# Dual_LPF_V1_2_Top.net
KiCad netlist of a schematic drawn in EAGLE
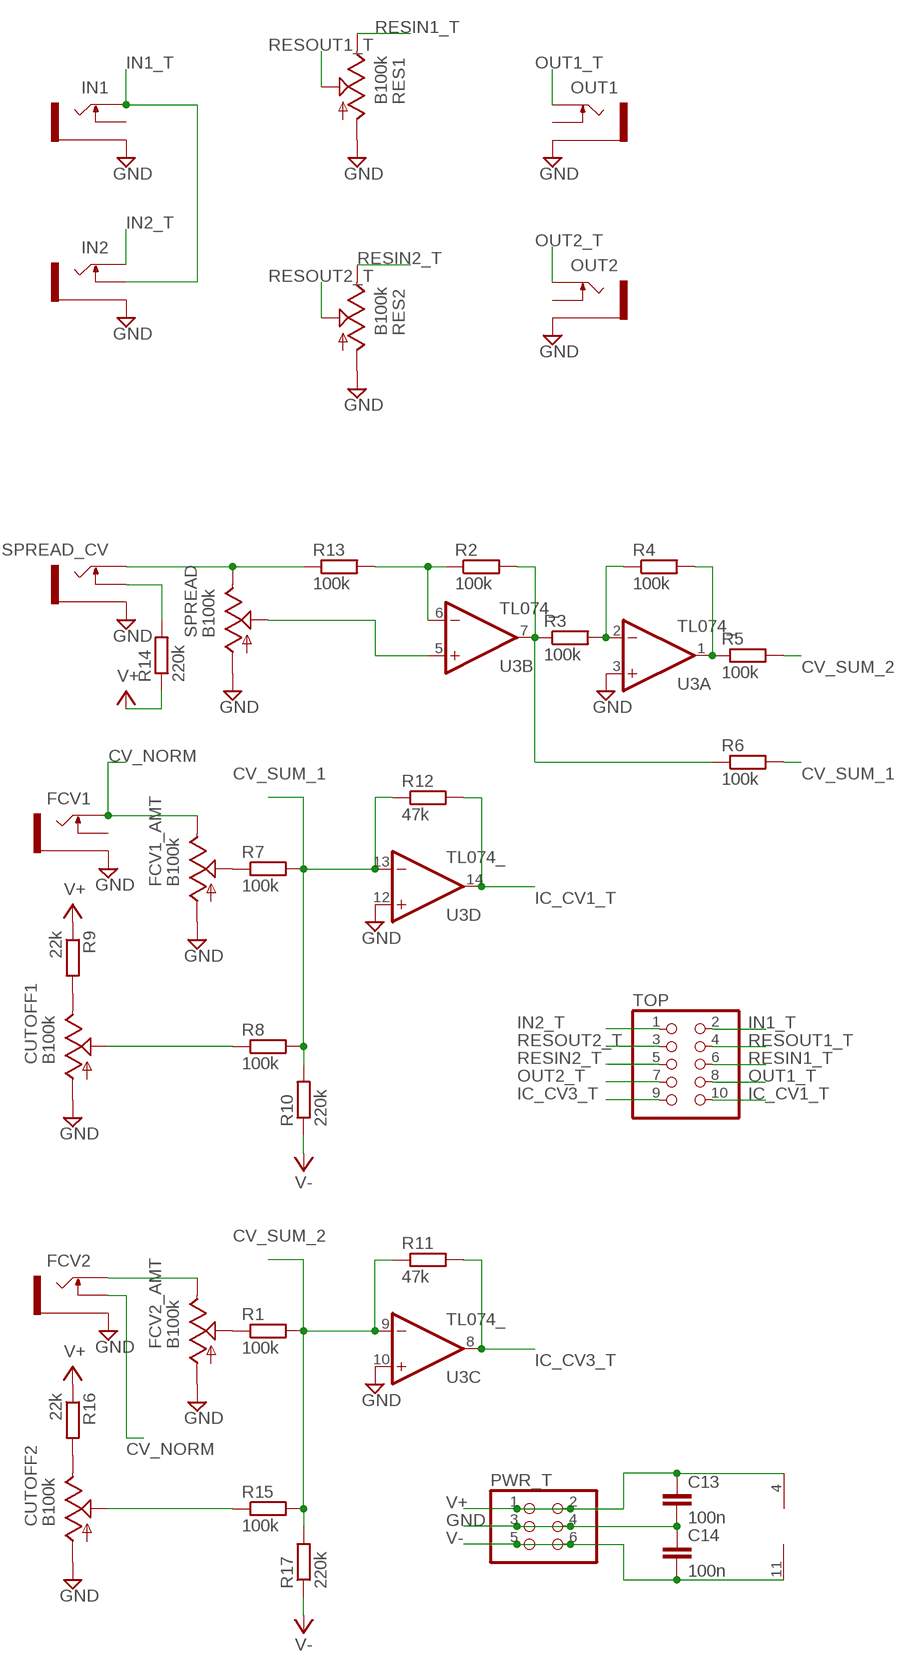
[diagram p0: schematic, sheet 1]

(export (version "E")
  (design (tool "Eeschema 10.0.6"))
  (components
    (comp (ref "C13")
      (value "100n")
      (footprint "eagle-import:C050-024X044")
      (libsource (lib "eagle-import") (part "C-EU050-024X044"))
    )
    (comp (ref "C14")
      (value "100n")
      (footprint "eagle-import:C050-024X044")
      (libsource (lib "eagle-import") (part "C-EU050-024X044"))
    )
    (comp (ref "CUTOFF1")
      (value "B100k")
      (footprint "eagle-import:9MM_SNAP-IN_POT")
      (libsource (lib "eagle-import") (part "9MM_SNAP-IN_POT_"))
    )
    (comp (ref "CUTOFF2")
      (value "B100k")
      (footprint "eagle-import:9MM_SNAP-IN_POT")
      (libsource (lib "eagle-import") (part "9MM_SNAP-IN_POT_"))
    )
    (comp (ref "FCV1")
      (value "THONKICONNNEW")
      (footprint "eagle-import:WQP-PJ301M-12_JACK")
      (libsource (lib "eagle-import") (part "THONKICONNNEW"))
    )
    (comp (ref "FCV1_AMT")
      (value "B100k")
      (footprint "eagle-import:9MM_SNAP-IN_POT")
      (libsource (lib "eagle-import") (part "9MM_SNAP-IN_POT_"))
    )
    (comp (ref "FCV2")
      (value "THONKICONNNEW")
      (footprint "eagle-import:WQP-PJ301M-12_JACK")
      (libsource (lib "eagle-import") (part "THONKICONNNEW"))
    )
    (comp (ref "FCV2_AMT")
      (value "B100k")
      (footprint "eagle-import:9MM_SNAP-IN_POT")
      (libsource (lib "eagle-import") (part "9MM_SNAP-IN_POT_"))
    )
    (comp (ref "IN1")
      (value "THONKICONNNEW")
      (footprint "eagle-import:WQP-PJ301M-12_JACK")
      (libsource (lib "eagle-import") (part "THONKICONNNEW"))
    )
    (comp (ref "IN2")
      (value "THONKICONNNEW")
      (footprint "eagle-import:WQP-PJ301M-12_JACK")
      (libsource (lib "eagle-import") (part "THONKICONNNEW"))
    )
    (comp (ref "OUT1")
      (value "THONKICONNNEW")
      (footprint "eagle-import:WQP-PJ301M-12_JACK")
      (libsource (lib "eagle-import") (part "THONKICONNNEW"))
    )
    (comp (ref "OUT2")
      (value "THONKICONNNEW")
      (footprint "eagle-import:WQP-PJ301M-12_JACK")
      (libsource (lib "eagle-import") (part "THONKICONNNEW"))
    )
    (comp (ref "PWR_T")
      (value "PINHD-2X3")
      (footprint "eagle-import:2X03")
      (libsource (lib "eagle-import") (part "PINHD-2X3"))
    )
    (comp (ref "R1")
      (value "100k")
      (footprint "eagle-import:0207_7")
      (libsource (lib "eagle-import") (part "R-EU_0207/7"))
    )
    (comp (ref "R2")
      (value "100k")
      (footprint "eagle-import:0207_7")
      (libsource (lib "eagle-import") (part "R-EU_0207/7"))
    )
    (comp (ref "R3")
      (value "100k")
      (footprint "eagle-import:0207_7")
      (libsource (lib "eagle-import") (part "R-EU_0207/7"))
    )
    (comp (ref "R4")
      (value "100k")
      (footprint "eagle-import:0207_7")
      (libsource (lib "eagle-import") (part "R-EU_0207/7"))
    )
    (comp (ref "R5")
      (value "100k")
      (footprint "eagle-import:0207_7")
      (libsource (lib "eagle-import") (part "R-EU_0207/7"))
    )
    (comp (ref "R6")
      (value "100k")
      (footprint "eagle-import:0207_7")
      (libsource (lib "eagle-import") (part "R-EU_0207/7"))
    )
    (comp (ref "R7")
      (value "100k")
      (footprint "eagle-import:0207_7")
      (libsource (lib "eagle-import") (part "R-EU_0207/7"))
    )
    (comp (ref "R8")
      (value "100k")
      (footprint "eagle-import:0207_7")
      (libsource (lib "eagle-import") (part "R-EU_0207/7"))
    )
    (comp (ref "R9")
      (value "22k")
      (footprint "eagle-import:0207_7")
      (libsource (lib "eagle-import") (part "R-EU_0207/7"))
    )
    (comp (ref "R10")
      (value "220k")
      (footprint "eagle-import:0207_7")
      (libsource (lib "eagle-import") (part "R-EU_0207/7"))
    )
    (comp (ref "R11")
      (value "47k")
      (footprint "eagle-import:0207_7")
      (libsource (lib "eagle-import") (part "R-EU_0207/7"))
    )
    (comp (ref "R12")
      (value "47k")
      (footprint "eagle-import:0207_7")
      (libsource (lib "eagle-import") (part "R-EU_0207/7"))
    )
    (comp (ref "R13")
      (value "100k")
      (footprint "eagle-import:0207_7")
      (libsource (lib "eagle-import") (part "R-EU_0207/7"))
    )
    (comp (ref "R14")
      (value "220k")
      (footprint "eagle-import:0207_7")
      (libsource (lib "eagle-import") (part "R-EU_0207/7"))
    )
    (comp (ref "R15")
      (value "100k")
      (footprint "eagle-import:0207_7")
      (libsource (lib "eagle-import") (part "R-EU_0207/7"))
    )
    (comp (ref "R16")
      (value "22k")
      (footprint "eagle-import:0207_7")
      (libsource (lib "eagle-import") (part "R-EU_0207/7"))
    )
    (comp (ref "R17")
      (value "220k")
      (footprint "eagle-import:0207_7")
      (libsource (lib "eagle-import") (part "R-EU_0207/7"))
    )
    (comp (ref "RES1")
      (value "B100k")
      (footprint "eagle-import:9MM_SNAP-IN_POT")
      (libsource (lib "eagle-import") (part "9MM_SNAP-IN_POT_"))
    )
    (comp (ref "RES2")
      (value "B100k")
      (footprint "eagle-import:9MM_SNAP-IN_POT")
      (libsource (lib "eagle-import") (part "9MM_SNAP-IN_POT_"))
    )
    (comp (ref "SPREAD")
      (value "B100k")
      (footprint "eagle-import:9MM_SNAP-IN_POT")
      (libsource (lib "eagle-import") (part "9MM_SNAP-IN_POT_"))
    )
    (comp (ref "SPREAD_CV")
      (value "THONKICONNNEW")
      (footprint "eagle-import:WQP-PJ301M-12_JACK")
      (libsource (lib "eagle-import") (part "THONKICONNNEW"))
    )
    (comp (ref "TOP")
      (value "PINHD-2X5")
      (footprint "eagle-import:2X05")
      (libsource (lib "eagle-import") (part "PINHD-2X5"))
    )
    (comp (ref "U3")
      (value "TL074_")
      (footprint "eagle-import:DIL14")
      (libsource (lib "eagle-import") (part "TL074_"))
    )
  )
  (nets
    (net (code "1") (name "/CV_NORM") (class "Default")
      (node (ref "FCV1") (pin "P$1_TIP") (pinfunction "TIP_P$1_TIP") (pintype "passive"))
      (node (ref "FCV1_AMT") (pin "3") (pinfunction "E_3") (pintype "passive"))
      (node (ref "FCV2") (pin "P$2_SWITCH") (pinfunction "SWITCH_P$2_SWITCH") (pintype "passive"))
    )
    (net (code "2") (name "/CV_SUM_1") (class "Default")
      (node (ref "R10") (pin "2") (pinfunction "2_2") (pintype "passive"))
      (node (ref "R12") (pin "1") (pinfunction "1_1") (pintype "passive"))
      (node (ref "R6") (pin "2") (pinfunction "2_2") (pintype "passive"))
      (node (ref "R7") (pin "2") (pinfunction "2_2") (pintype "passive"))
      (node (ref "R8") (pin "2") (pinfunction "2_2") (pintype "passive"))
      (node (ref "U3") (pin "13") (pinfunction "-IN_13") (pintype "input"))
    )
    (net (code "3") (name "/CV_SUM_2") (class "Default")
      (node (ref "R1") (pin "2") (pinfunction "2_2") (pintype "passive"))
      (node (ref "R11") (pin "1") (pinfunction "1_1") (pintype "passive"))
      (node (ref "R15") (pin "2") (pinfunction "2_2") (pintype "passive"))
      (node (ref "R17") (pin "2") (pinfunction "2_2") (pintype "passive"))
      (node (ref "R5") (pin "2") (pinfunction "2_2") (pintype "passive"))
      (node (ref "U3") (pin "9") (pinfunction "-IN_9") (pintype "input"))
    )
    (net (code "4") (name "/IC_CV1_T") (class "Default")
      (node (ref "R12") (pin "2") (pinfunction "2_2") (pintype "passive"))
      (node (ref "TOP") (pin "10") (pinfunction "10_10") (pintype "passive"))
      (node (ref "U3") (pin "14") (pinfunction "OUT_14") (pintype "output"))
    )
    (net (code "5") (name "/IC_CV3_T") (class "Default")
      (node (ref "R11") (pin "2") (pinfunction "2_2") (pintype "passive"))
      (node (ref "TOP") (pin "9") (pinfunction "9_9") (pintype "passive"))
      (node (ref "U3") (pin "8") (pinfunction "OUT_8") (pintype "output"))
    )
    (net (code "6") (name "/IN1_T") (class "Default")
      (node (ref "IN1") (pin "P$1_TIP") (pinfunction "TIP_P$1_TIP") (pintype "passive"))
      (node (ref "IN2") (pin "P$2_SWITCH") (pinfunction "SWITCH_P$2_SWITCH") (pintype "passive"))
      (node (ref "TOP") (pin "2") (pinfunction "2_2") (pintype "passive"))
    )
    (net (code "7") (name "/IN2_T") (class "Default")
      (node (ref "IN2") (pin "P$1_TIP") (pinfunction "TIP_P$1_TIP") (pintype "passive"))
      (node (ref "TOP") (pin "1") (pinfunction "1_1") (pintype "passive"))
    )
    (net (code "8") (name "/OUT1_T") (class "Default")
      (node (ref "OUT1") (pin "P$1_TIP") (pinfunction "TIP_P$1_TIP") (pintype "passive"))
      (node (ref "TOP") (pin "8") (pinfunction "8_8") (pintype "passive"))
    )
    (net (code "9") (name "/OUT2_T") (class "Default")
      (node (ref "OUT2") (pin "P$1_TIP") (pinfunction "TIP_P$1_TIP") (pintype "passive"))
      (node (ref "TOP") (pin "7") (pinfunction "7_7") (pintype "passive"))
    )
    (net (code "10") (name "/RESIN1_T") (class "Default")
      (node (ref "RES1") (pin "3") (pinfunction "E_3") (pintype "passive"))
      (node (ref "TOP") (pin "6") (pinfunction "6_6") (pintype "passive"))
    )
    (net (code "11") (name "/RESIN2_T") (class "Default")
      (node (ref "RES2") (pin "3") (pinfunction "E_3") (pintype "passive"))
      (node (ref "TOP") (pin "5") (pinfunction "5_5") (pintype "passive"))
    )
    (net (code "12") (name "/RESOUT1_T") (class "Default")
      (node (ref "RES1") (pin "2") (pinfunction "S_2") (pintype "passive"))
      (node (ref "TOP") (pin "4") (pinfunction "4_4") (pintype "passive"))
    )
    (net (code "13") (name "/RESOUT2_T") (class "Default")
      (node (ref "RES2") (pin "2") (pinfunction "S_2") (pintype "passive"))
      (node (ref "TOP") (pin "3") (pinfunction "3_3") (pintype "passive"))
    )
    (net (code "14") (name "GND") (class "Default")
      (node (ref "C13") (pin "2") (pinfunction "2_2") (pintype "passive"))
      (node (ref "C14") (pin "1") (pinfunction "1_1") (pintype "passive"))
      (node (ref "CUTOFF1") (pin "1") (pinfunction "A_1") (pintype "passive"))
      (node (ref "CUTOFF2") (pin "1") (pinfunction "A_1") (pintype "passive"))
      (node (ref "FCV1") (pin "P$3_SLEEVE") (pinfunction "SLEEVE_P$3_SLEEVE") (pintype "passive"))
      (node (ref "FCV1_AMT") (pin "1") (pinfunction "A_1") (pintype "passive"))
      (node (ref "FCV2") (pin "P$3_SLEEVE") (pinfunction "SLEEVE_P$3_SLEEVE") (pintype "passive"))
      (node (ref "FCV2_AMT") (pin "1") (pinfunction "A_1") (pintype "passive"))
      (node (ref "IN1") (pin "P$3_SLEEVE") (pinfunction "SLEEVE_P$3_SLEEVE") (pintype "passive"))
      (node (ref "IN2") (pin "P$3_SLEEVE") (pinfunction "SLEEVE_P$3_SLEEVE") (pintype "passive"))
      (node (ref "OUT1") (pin "P$3_SLEEVE") (pinfunction "SLEEVE_P$3_SLEEVE") (pintype "passive"))
      (node (ref "OUT2") (pin "P$3_SLEEVE") (pinfunction "SLEEVE_P$3_SLEEVE") (pintype "passive"))
      (node (ref "PWR_T") (pin "3") (pinfunction "3_3") (pintype "passive"))
      (node (ref "PWR_T") (pin "4") (pinfunction "4_4") (pintype "passive"))
      (node (ref "RES1") (pin "1") (pinfunction "A_1") (pintype "passive"))
      (node (ref "RES2") (pin "1") (pinfunction "A_1") (pintype "passive"))
      (node (ref "SPREAD") (pin "1") (pinfunction "A_1") (pintype "passive"))
      (node (ref "SPREAD_CV") (pin "P$3_SLEEVE") (pinfunction "SLEEVE_P$3_SLEEVE") (pintype "passive"))
      (node (ref "U3") (pin "10") (pinfunction "+IN_10") (pintype "input"))
      (node (ref "U3") (pin "12") (pinfunction "+IN_12") (pintype "input"))
      (node (ref "U3") (pin "3") (pinfunction "+IN_3") (pintype "input"))
    )
    (net (code "15") (name "Net-(CUTOFF1-E)") (class "Default")
      (node (ref "CUTOFF1") (pin "3") (pinfunction "E_3") (pintype "passive"))
      (node (ref "R9") (pin "2") (pinfunction "2_2") (pintype "passive"))
    )
    (net (code "16") (name "Net-(CUTOFF1-S)") (class "Default")
      (node (ref "CUTOFF1") (pin "2") (pinfunction "S_2") (pintype "passive"))
      (node (ref "R8") (pin "1") (pinfunction "1_1") (pintype "passive"))
    )
    (net (code "17") (name "Net-(CUTOFF2-E)") (class "Default")
      (node (ref "CUTOFF2") (pin "3") (pinfunction "E_3") (pintype "passive"))
      (node (ref "R16") (pin "2") (pinfunction "2_2") (pintype "passive"))
    )
    (net (code "18") (name "Net-(CUTOFF2-S)") (class "Default")
      (node (ref "CUTOFF2") (pin "2") (pinfunction "S_2") (pintype "passive"))
      (node (ref "R15") (pin "1") (pinfunction "1_1") (pintype "passive"))
    )
    (net (code "19") (name "Net-(FCV1_AMT-S)") (class "Default")
      (node (ref "FCV1_AMT") (pin "2") (pinfunction "S_2") (pintype "passive"))
      (node (ref "R7") (pin "1") (pinfunction "1_1") (pintype "passive"))
    )
    (net (code "20") (name "Net-(FCV2-TIP)") (class "Default")
      (node (ref "FCV2") (pin "P$1_TIP") (pinfunction "TIP_P$1_TIP") (pintype "passive"))
      (node (ref "FCV2_AMT") (pin "3") (pinfunction "E_3") (pintype "passive"))
    )
    (net (code "21") (name "Net-(FCV2_AMT-S)") (class "Default")
      (node (ref "FCV2_AMT") (pin "2") (pinfunction "S_2") (pintype "passive"))
      (node (ref "R1") (pin "1") (pinfunction "1_1") (pintype "passive"))
    )
    (net (code "22") (name "Net-(SPREAD-E)") (class "Default")
      (node (ref "R13") (pin "1") (pinfunction "1_1") (pintype "passive"))
      (node (ref "SPREAD") (pin "3") (pinfunction "E_3") (pintype "passive"))
      (node (ref "SPREAD_CV") (pin "P$1_TIP") (pinfunction "TIP_P$1_TIP") (pintype "passive"))
    )
    (net (code "23") (name "Net-(SPREAD-S)") (class "Default")
      (node (ref "SPREAD") (pin "2") (pinfunction "S_2") (pintype "passive"))
      (node (ref "U3") (pin "5") (pinfunction "+IN_5") (pintype "input"))
    )
    (net (code "24") (name "Net-(SPREAD_CV-SWITCH)") (class "Default")
      (node (ref "R14") (pin "2") (pinfunction "2_2") (pintype "passive"))
      (node (ref "SPREAD_CV") (pin "P$2_SWITCH") (pinfunction "SWITCH_P$2_SWITCH") (pintype "passive"))
    )
    (net (code "25") (name "Net-(U3A--IN)") (class "Default")
      (node (ref "R3") (pin "2") (pinfunction "2_2") (pintype "passive"))
      (node (ref "R4") (pin "1") (pinfunction "1_1") (pintype "passive"))
      (node (ref "U3") (pin "2") (pinfunction "-IN_2") (pintype "input"))
    )
    (net (code "26") (name "Net-(U3A-OUT)") (class "Default")
      (node (ref "R4") (pin "2") (pinfunction "2_2") (pintype "passive"))
      (node (ref "R5") (pin "1") (pinfunction "1_1") (pintype "passive"))
      (node (ref "U3") (pin "1") (pinfunction "OUT_1") (pintype "output"))
    )
    (net (code "27") (name "Net-(U3B--IN)") (class "Default")
      (node (ref "R13") (pin "2") (pinfunction "2_2") (pintype "passive"))
      (node (ref "R2") (pin "1") (pinfunction "1_1") (pintype "passive"))
      (node (ref "U3") (pin "6") (pinfunction "-IN_6") (pintype "input"))
    )
    (net (code "28") (name "Net-(U3B-OUT)") (class "Default")
      (node (ref "R2") (pin "2") (pinfunction "2_2") (pintype "passive"))
      (node (ref "R3") (pin "1") (pinfunction "1_1") (pintype "passive"))
      (node (ref "R6") (pin "1") (pinfunction "1_1") (pintype "passive"))
      (node (ref "U3") (pin "7") (pinfunction "OUT_7") (pintype "output"))
    )
    (net (code "29") (name "V+") (class "Default")
      (node (ref "C13") (pin "1") (pinfunction "1_1") (pintype "passive"))
      (node (ref "PWR_T") (pin "1") (pinfunction "1_1") (pintype "passive"))
      (node (ref "PWR_T") (pin "2") (pinfunction "2_2") (pintype "passive"))
      (node (ref "R14") (pin "1") (pinfunction "1_1") (pintype "passive"))
      (node (ref "R16") (pin "1") (pinfunction "1_1") (pintype "passive"))
      (node (ref "R9") (pin "1") (pinfunction "1_1") (pintype "passive"))
      (node (ref "U3") (pin "4") (pinfunction "V+_4") (pintype "power_in"))
    )
    (net (code "30") (name "V-") (class "Default")
      (node (ref "C14") (pin "2") (pinfunction "2_2") (pintype "passive"))
      (node (ref "PWR_T") (pin "5") (pinfunction "5_5") (pintype "passive"))
      (node (ref "PWR_T") (pin "6") (pinfunction "6_6") (pintype "passive"))
      (node (ref "R10") (pin "1") (pinfunction "1_1") (pintype "passive"))
      (node (ref "R17") (pin "1") (pinfunction "1_1") (pintype "passive"))
      (node (ref "U3") (pin "11") (pinfunction "V-_11") (pintype "power_in"))
    )
    (net (code "31") (name "unconnected-(FCV1-SWITCH-PadP$2_SWITCH)") (class "Default")
      (node (ref "FCV1") (pin "P$2_SWITCH") (pinfunction "SWITCH_P$2_SWITCH") (pintype "passive"))
    )
    (net (code "32") (name "unconnected-(IN1-SWITCH-PadP$2_SWITCH)") (class "Default")
      (node (ref "IN1") (pin "P$2_SWITCH") (pinfunction "SWITCH_P$2_SWITCH") (pintype "passive"))
    )
    (net (code "33") (name "unconnected-(OUT1-SWITCH-PadP$2_SWITCH)") (class "Default")
      (node (ref "OUT1") (pin "P$2_SWITCH") (pinfunction "SWITCH_P$2_SWITCH") (pintype "passive"))
    )
    (net (code "34") (name "unconnected-(OUT2-SWITCH-PadP$2_SWITCH)") (class "Default")
      (node (ref "OUT2") (pin "P$2_SWITCH") (pinfunction "SWITCH_P$2_SWITCH") (pintype "passive"))
    )
  )
)
